# crystal-test-breakout.net
KiCad netlist of a schematic drawn in EAGLE
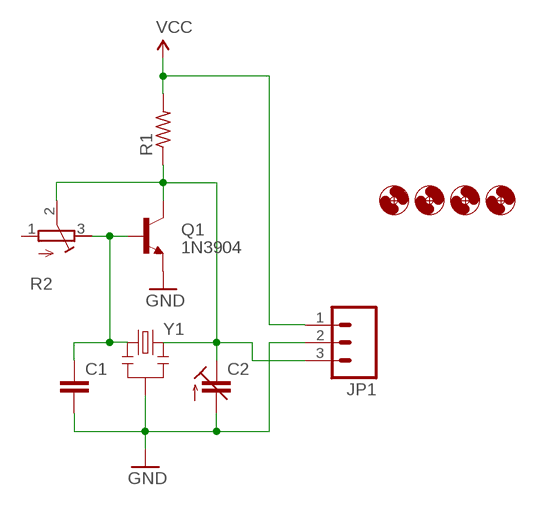
[diagram p0: schematic, sheet 1]

(export (version "E")
  (design (tool "Eeschema 10.0.6"))
  (components
    (comp (ref "C1")
      (value "CAPACITOR-CERAMIC025-025X050")
      (footprint "eagle-import:C025-025X050")
      (libsource (lib "eagle-import") (part "CAPACITOR-CERAMIC025-025X050"))
    )
    (comp (ref "C2")
      (value "CAPACITOR-TRIM3050.504")
      (footprint "eagle-import:CTRIM3050.504")
      (libsource (lib "eagle-import") (part "CAPACITOR-TRIM3050.504"))
    )
    (comp (ref "H1")
      (value "HOLE#2")
      (footprint "eagle-import:HOLE-#2")
      (libsource (lib "eagle-import") (part "HOLE#2"))
    )
    (comp (ref "H2")
      (value "HOLE#2")
      (footprint "eagle-import:HOLE-#2")
      (libsource (lib "eagle-import") (part "HOLE#2"))
    )
    (comp (ref "H3")
      (value "HOLE#2")
      (footprint "eagle-import:HOLE-#2")
      (libsource (lib "eagle-import") (part "HOLE#2"))
    )
    (comp (ref "H4")
      (value "HOLE#2")
      (footprint "eagle-import:HOLE-#2")
      (libsource (lib "eagle-import") (part "HOLE#2"))
    )
    (comp (ref "JP1")
      (value "M03PTH")
      (footprint "eagle-import:1X03")
      (libsource (lib "eagle-import") (part "M03PTH"))
    )
    (comp (ref "Q1")
      (value "1N3904")
      (footprint "eagle-import:TO-92-AMMO")
      (libsource (lib "eagle-import") (part "TRANSISTOR_NPNTO-92-AMMO-EBC"))
    )
    (comp (ref "R1")
      (value "RESISTORPTH-AXIAL-5.08MM")
      (footprint "eagle-import:RESISTOR-AXIAL-PTH-5.08MM")
      (libsource (lib "eagle-import") (part "RESISTORPTH-AXIAL-5.08MM"))
    )
    (comp (ref "R2")
      (value "POTENTIOMETER3296W-SIDE")
      (footprint "eagle-import:RTRIM3296W-SIDEWAYS")
      (libsource (lib "eagle-import") (part "POTENTIOMETER3296W-SIDE"))
    )
    (comp (ref "Y1")
      (value "RESONATORPTH")
      (footprint "eagle-import:RESONATOR-PTH")
      (libsource (lib "eagle-import") (part "RESONATORPTH"))
    )
  )
  (nets
    (net (code "1") (name "GND") (class "Default")
      (node (ref "C1") (pin "2") (pinfunction "2_2") (pintype "passive"))
      (node (ref "C2") (pin "2") (pinfunction "A_2") (pintype "passive"))
      (node (ref "JP1") (pin "2") (pinfunction "2_2") (pintype "passive"))
      (node (ref "Q1") (pin "1") (pinfunction "E_1") (pintype "passive"))
      (node (ref "Y1") (pin "2") (pinfunction "2_2") (pintype "passive"))
    )
    (net (code "2") (name "Net-(C2-E)") (class "Default")
      (node (ref "C2") (pin "1") (pinfunction "E_1") (pintype "passive"))
      (node (ref "JP1") (pin "3") (pinfunction "3_3") (pintype "passive"))
      (node (ref "Q1") (pin "3") (pinfunction "C_3") (pintype "passive"))
      (node (ref "R1") (pin "P$1") (pinfunction "1_P$1") (pintype "passive"))
      (node (ref "R2") (pin "2") (pinfunction "S_2") (pintype "passive"))
      (node (ref "Y1") (pin "3") (pinfunction "3_3") (pintype "passive"))
    )
    (net (code "3") (name "Net-(Q1-B)") (class "Default")
      (node (ref "C1") (pin "1") (pinfunction "1_1") (pintype "passive"))
      (node (ref "Q1") (pin "2") (pinfunction "B_2") (pintype "passive"))
      (node (ref "R2") (pin "3") (pinfunction "E_3") (pintype "passive"))
      (node (ref "Y1") (pin "1") (pinfunction "1_1") (pintype "passive"))
    )
    (net (code "4") (name "VCC") (class "Default")
      (node (ref "JP1") (pin "1") (pinfunction "1_1") (pintype "passive"))
      (node (ref "R1") (pin "P$2") (pinfunction "2_P$2") (pintype "passive"))
    )
    (net (code "5") (name "unconnected-(R2-A-Pad1)") (class "Default")
      (node (ref "R2") (pin "1") (pinfunction "A_1") (pintype "passive"))
    )
  )
)
